# M206C.net
KiCad netlist of a schematic drawn in EAGLE
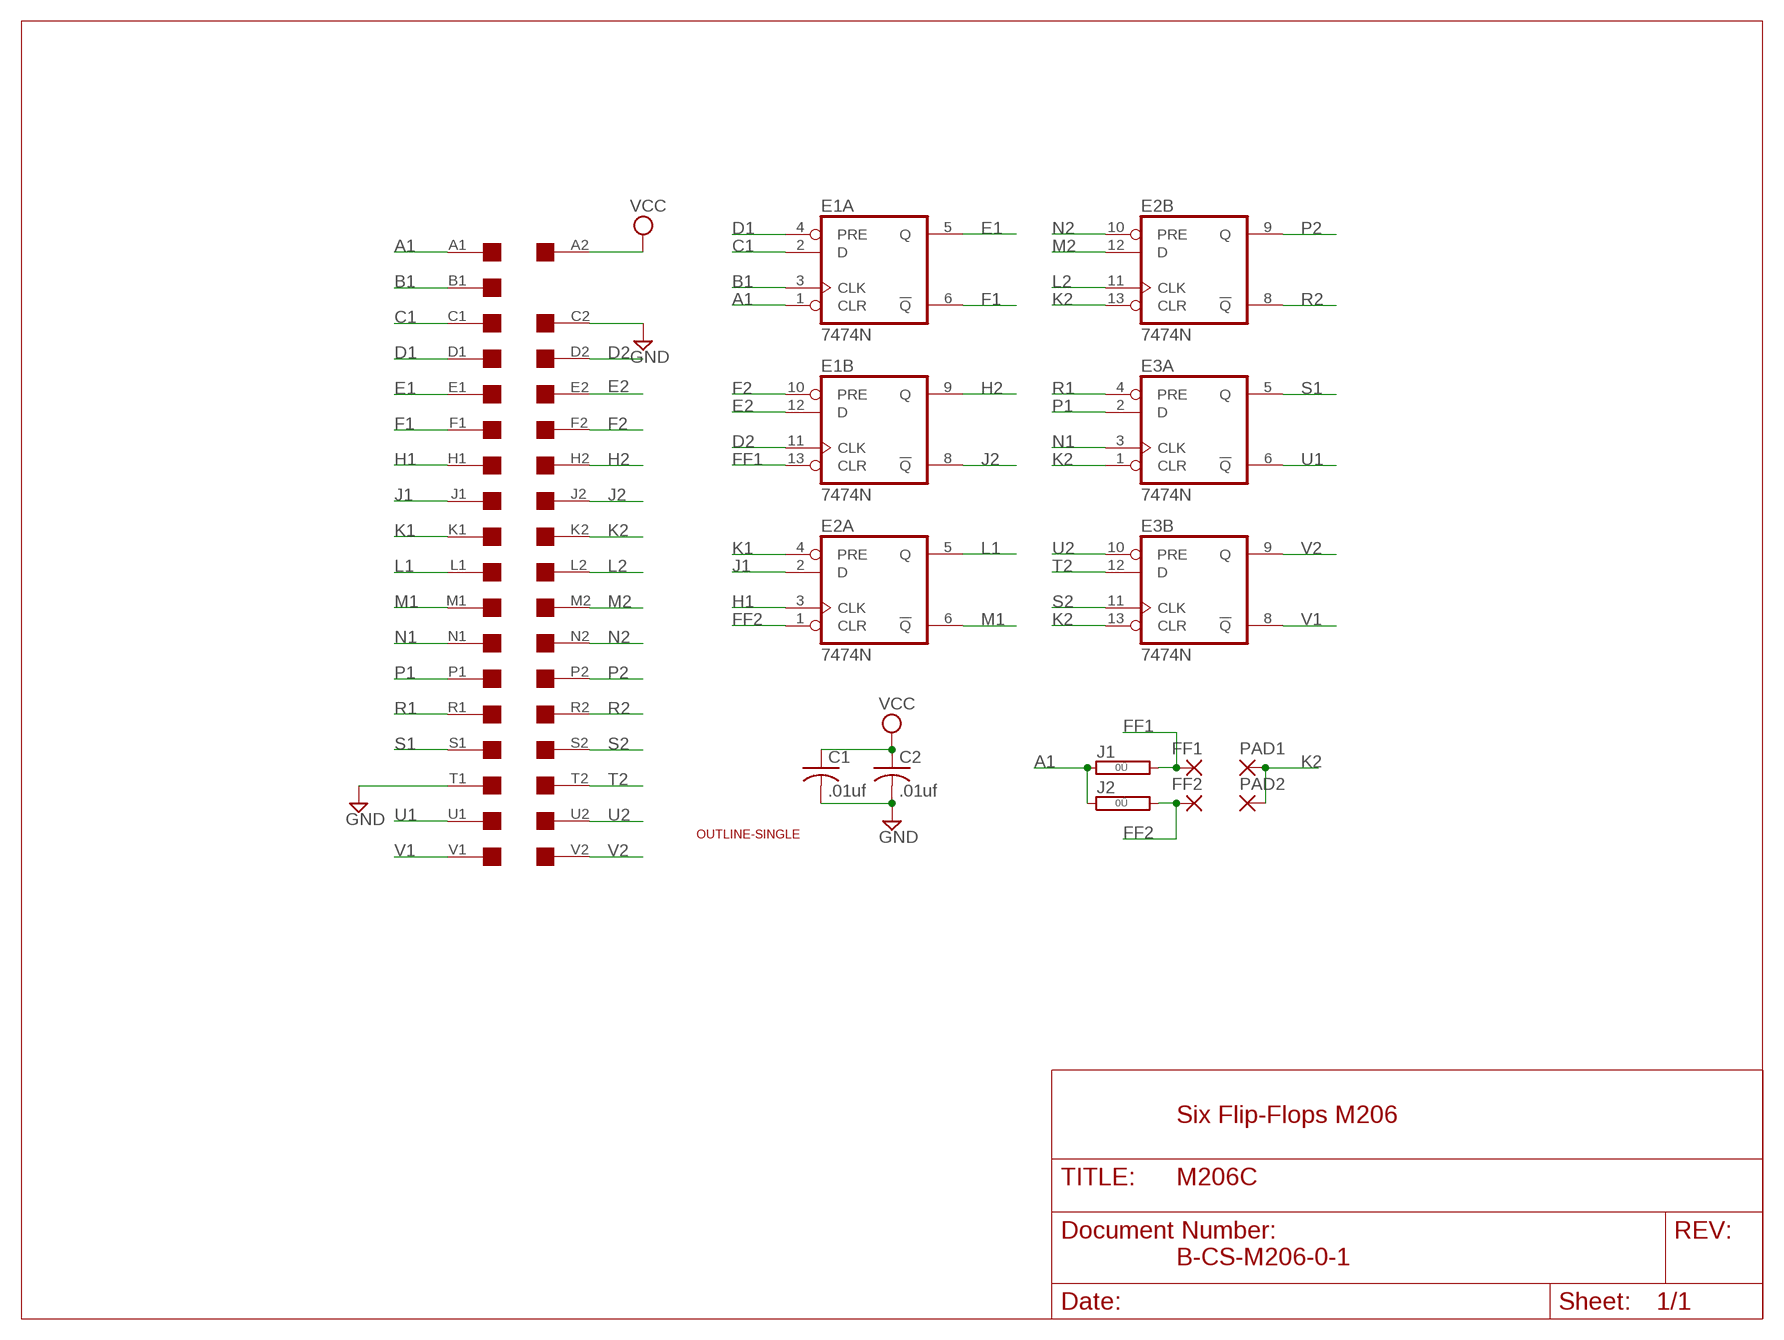
[diagram p0: schematic, sheet 1]

(export (version "E")
  (design (tool "Eeschema 10.0.6"))
  (components
    (comp (ref "C1")
      (value ".01uf")
      (footprint "eagle-import:C050-025X075")
      (libsource (lib "eagle-import") (part "C-US050-025X075"))
    )
    (comp (ref "C2")
      (value ".01uf")
      (footprint "eagle-import:C050-025X075")
      (libsource (lib "eagle-import") (part "C-US050-025X075"))
    )
    (comp (ref "E1")
      (value "7474N")
      (footprint "eagle-import:DIL14")
      (libsource (lib "eagle-import") (part "7474NS"))
    )
    (comp (ref "E2")
      (value "7474N")
      (footprint "eagle-import:DIL14")
      (libsource (lib "eagle-import") (part "7474NS"))
    )
    (comp (ref "E3")
      (value "7474N")
      (footprint "eagle-import:DIL14")
      (libsource (lib "eagle-import") (part "7474NS"))
    )
    (comp (ref "FF1")
      (value "1,6/0,8")
      (footprint "eagle-import:1,6_0,8")
      (libsource (lib "eagle-import") (part "1,6/0,8"))
    )
    (comp (ref "FF2")
      (value "1,6/0,8")
      (footprint "eagle-import:1,6_0,8")
      (libsource (lib "eagle-import") (part "1,6/0,8"))
    )
    (comp (ref "J1")
      (value "0R")
      (footprint "eagle-import:0R_10")
      (libsource (lib "eagle-import") (part "0R"))
    )
    (comp (ref "J2")
      (value "0R")
      (footprint "eagle-import:0R_10")
      (libsource (lib "eagle-import") (part "0R"))
    )
    (comp (ref "PAD1")
      (value "1,6/0,8")
      (footprint "eagle-import:1,6_0,8")
      (libsource (lib "eagle-import") (part "1,6/0,8"))
    )
    (comp (ref "PAD2")
      (value "1,6/0,8")
      (footprint "eagle-import:1,6_0,8")
      (libsource (lib "eagle-import") (part "1,6/0,8"))
    )
    (comp (ref "U$1")
      (value "OUTLINE-SINGLE")
      (footprint "eagle-import:SINGLE")
      (libsource (lib "eagle-import") (part "OUTLINE-SINGLE"))
    )
    (comp (ref "U$4")
      (value "SINGLE")
      (footprint "eagle-import:EDGE-CON2")
      (libsource (lib "eagle-import") (part "SINGLE"))
    )
  )
  (nets
    (net (code "1") (name "/A1") (class "Default")
      (node (ref "E1") (pin "1") (pinfunction "CLR_1") (pintype "input"))
      (node (ref "J1") (pin "1") (pinfunction "1_1") (pintype "passive"))
      (node (ref "J2") (pin "1") (pinfunction "1_1") (pintype "passive"))
      (node (ref "U$4") (pin "A1") (pinfunction "1_A1") (pintype "bidirectional"))
    )
    (net (code "2") (name "/B1") (class "Default")
      (node (ref "E1") (pin "3") (pinfunction "CLK_3") (pintype "input"))
      (node (ref "U$4") (pin "B1") (pinfunction "1_B1") (pintype "bidirectional"))
    )
    (net (code "3") (name "/C1") (class "Default")
      (node (ref "E1") (pin "2") (pinfunction "D_2") (pintype "input"))
      (node (ref "U$4") (pin "C1") (pinfunction "1_C1") (pintype "bidirectional"))
    )
    (net (code "4") (name "/D1") (class "Default")
      (node (ref "E1") (pin "4") (pinfunction "PRE_4") (pintype "input"))
      (node (ref "U$4") (pin "D1") (pinfunction "1_D1") (pintype "bidirectional"))
    )
    (net (code "5") (name "/D2") (class "Default")
      (node (ref "E1") (pin "11") (pinfunction "CLK_11") (pintype "input"))
      (node (ref "U$4") (pin "D2") (pinfunction "1_D2") (pintype "bidirectional"))
    )
    (net (code "6") (name "/E1") (class "Default")
      (node (ref "E1") (pin "5") (pinfunction "Q_5") (pintype "output"))
      (node (ref "U$4") (pin "E1") (pinfunction "1_E1") (pintype "bidirectional"))
    )
    (net (code "7") (name "/E2") (class "Default")
      (node (ref "E1") (pin "12") (pinfunction "D_12") (pintype "input"))
      (node (ref "U$4") (pin "E2") (pinfunction "1_E2") (pintype "bidirectional"))
    )
    (net (code "8") (name "/F1") (class "Default")
      (node (ref "E1") (pin "6") (pinfunction "~{Q}_6") (pintype "output"))
      (node (ref "U$4") (pin "F1") (pinfunction "1_F1") (pintype "bidirectional"))
    )
    (net (code "9") (name "/F2") (class "Default")
      (node (ref "E1") (pin "10") (pinfunction "PRE_10") (pintype "input"))
      (node (ref "U$4") (pin "F2") (pinfunction "1_F2") (pintype "bidirectional"))
    )
    (net (code "10") (name "/FF1") (class "Default")
      (node (ref "E1") (pin "13") (pinfunction "CLR_13") (pintype "input"))
      (node (ref "FF1") (pin "1") (pinfunction "P_1") (pintype "passive"))
      (node (ref "J1") (pin "2") (pinfunction "2_2") (pintype "passive"))
    )
    (net (code "11") (name "/FF2") (class "Default")
      (node (ref "E2") (pin "1") (pinfunction "CLR_1") (pintype "input"))
      (node (ref "FF2") (pin "1") (pinfunction "P_1") (pintype "passive"))
      (node (ref "J2") (pin "2") (pinfunction "2_2") (pintype "passive"))
    )
    (net (code "12") (name "/H1") (class "Default")
      (node (ref "E2") (pin "3") (pinfunction "CLK_3") (pintype "input"))
      (node (ref "U$4") (pin "H1") (pinfunction "1_H1") (pintype "bidirectional"))
    )
    (net (code "13") (name "/H2") (class "Default")
      (node (ref "E1") (pin "9") (pinfunction "Q_9") (pintype "output"))
      (node (ref "U$4") (pin "H2") (pinfunction "1_H2") (pintype "bidirectional"))
    )
    (net (code "14") (name "/J1") (class "Default")
      (node (ref "E2") (pin "2") (pinfunction "D_2") (pintype "input"))
      (node (ref "U$4") (pin "J1") (pinfunction "1_J1") (pintype "bidirectional"))
    )
    (net (code "15") (name "/J2") (class "Default")
      (node (ref "E1") (pin "8") (pinfunction "~{Q}_8") (pintype "output"))
      (node (ref "U$4") (pin "J2") (pinfunction "1_J2") (pintype "bidirectional"))
    )
    (net (code "16") (name "/K1") (class "Default")
      (node (ref "E2") (pin "4") (pinfunction "PRE_4") (pintype "input"))
      (node (ref "U$4") (pin "K1") (pinfunction "1_K1") (pintype "bidirectional"))
    )
    (net (code "17") (name "/K2") (class "Default")
      (node (ref "E2") (pin "13") (pinfunction "CLR_13") (pintype "input"))
      (node (ref "E3") (pin "1") (pinfunction "CLR_1") (pintype "input"))
      (node (ref "E3") (pin "13") (pinfunction "CLR_13") (pintype "input"))
      (node (ref "PAD1") (pin "1") (pinfunction "P_1") (pintype "passive"))
      (node (ref "PAD2") (pin "1") (pinfunction "P_1") (pintype "passive"))
      (node (ref "U$4") (pin "K2") (pinfunction "1_K2") (pintype "bidirectional"))
    )
    (net (code "18") (name "/L1") (class "Default")
      (node (ref "E2") (pin "5") (pinfunction "Q_5") (pintype "output"))
      (node (ref "U$4") (pin "L1") (pinfunction "1_L1") (pintype "bidirectional"))
    )
    (net (code "19") (name "/L2") (class "Default")
      (node (ref "E2") (pin "11") (pinfunction "CLK_11") (pintype "input"))
      (node (ref "U$4") (pin "L2") (pinfunction "1_L2") (pintype "bidirectional"))
    )
    (net (code "20") (name "/M1") (class "Default")
      (node (ref "E2") (pin "6") (pinfunction "~{Q}_6") (pintype "output"))
      (node (ref "U$4") (pin "M1") (pinfunction "1_M1") (pintype "bidirectional"))
    )
    (net (code "21") (name "/M2") (class "Default")
      (node (ref "E2") (pin "12") (pinfunction "D_12") (pintype "input"))
      (node (ref "U$4") (pin "M2") (pinfunction "1_M2") (pintype "bidirectional"))
    )
    (net (code "22") (name "/N1") (class "Default")
      (node (ref "E3") (pin "3") (pinfunction "CLK_3") (pintype "input"))
      (node (ref "U$4") (pin "N1") (pinfunction "1_N1") (pintype "bidirectional"))
    )
    (net (code "23") (name "/N2") (class "Default")
      (node (ref "E2") (pin "10") (pinfunction "PRE_10") (pintype "input"))
      (node (ref "U$4") (pin "N2") (pinfunction "1_N2") (pintype "bidirectional"))
    )
    (net (code "24") (name "/P1") (class "Default")
      (node (ref "E3") (pin "2") (pinfunction "D_2") (pintype "input"))
      (node (ref "U$4") (pin "P1") (pinfunction "1_P1") (pintype "bidirectional"))
    )
    (net (code "25") (name "/P2") (class "Default")
      (node (ref "E2") (pin "9") (pinfunction "Q_9") (pintype "output"))
      (node (ref "U$4") (pin "P2") (pinfunction "1_P2") (pintype "bidirectional"))
    )
    (net (code "26") (name "/R1") (class "Default")
      (node (ref "E3") (pin "4") (pinfunction "PRE_4") (pintype "input"))
      (node (ref "U$4") (pin "R1") (pinfunction "1_R1") (pintype "bidirectional"))
    )
    (net (code "27") (name "/R2") (class "Default")
      (node (ref "E2") (pin "8") (pinfunction "~{Q}_8") (pintype "output"))
      (node (ref "U$4") (pin "R2") (pinfunction "1_R2") (pintype "bidirectional"))
    )
    (net (code "28") (name "/S1") (class "Default")
      (node (ref "E3") (pin "5") (pinfunction "Q_5") (pintype "output"))
      (node (ref "U$4") (pin "S1") (pinfunction "1_S1") (pintype "bidirectional"))
    )
    (net (code "29") (name "/S2") (class "Default")
      (node (ref "E3") (pin "11") (pinfunction "CLK_11") (pintype "input"))
      (node (ref "U$4") (pin "S2") (pinfunction "1_S2") (pintype "bidirectional"))
    )
    (net (code "30") (name "/T2") (class "Default")
      (node (ref "E3") (pin "12") (pinfunction "D_12") (pintype "input"))
      (node (ref "U$4") (pin "T2") (pinfunction "1_T2") (pintype "bidirectional"))
    )
    (net (code "31") (name "/U1") (class "Default")
      (node (ref "E3") (pin "6") (pinfunction "~{Q}_6") (pintype "output"))
      (node (ref "U$4") (pin "U1") (pinfunction "1_U1") (pintype "bidirectional"))
    )
    (net (code "32") (name "/U2") (class "Default")
      (node (ref "E3") (pin "10") (pinfunction "PRE_10") (pintype "input"))
      (node (ref "U$4") (pin "U2") (pinfunction "1_U2") (pintype "bidirectional"))
    )
    (net (code "33") (name "/V1") (class "Default")
      (node (ref "E3") (pin "8") (pinfunction "~{Q}_8") (pintype "output"))
      (node (ref "U$4") (pin "V1") (pinfunction "1_V1") (pintype "bidirectional"))
    )
    (net (code "34") (name "/V2") (class "Default")
      (node (ref "E3") (pin "9") (pinfunction "Q_9") (pintype "output"))
      (node (ref "U$4") (pin "V2") (pinfunction "1_V2") (pintype "bidirectional"))
    )
    (net (code "35") (name "GND") (class "Default")
      (node (ref "C1") (pin "2") (pinfunction "2_2") (pintype "passive"))
      (node (ref "C2") (pin "2") (pinfunction "2_2") (pintype "passive"))
      (node (ref "U$4") (pin "C2") (pinfunction "1_C2") (pintype "bidirectional"))
      (node (ref "U$4") (pin "T1") (pinfunction "1_T1") (pintype "bidirectional"))
    )
    (net (code "36") (name "VCC") (class "Default")
      (node (ref "C1") (pin "1") (pinfunction "1_1") (pintype "passive"))
      (node (ref "C2") (pin "1") (pinfunction "1_1") (pintype "passive"))
      (node (ref "U$4") (pin "A2") (pinfunction "1_A2") (pintype "bidirectional"))
    )
  )
)
